# Pressure_Rig_2020-12-04_14-32-13.net
KiCad netlist of a schematic drawn in EasyEDA
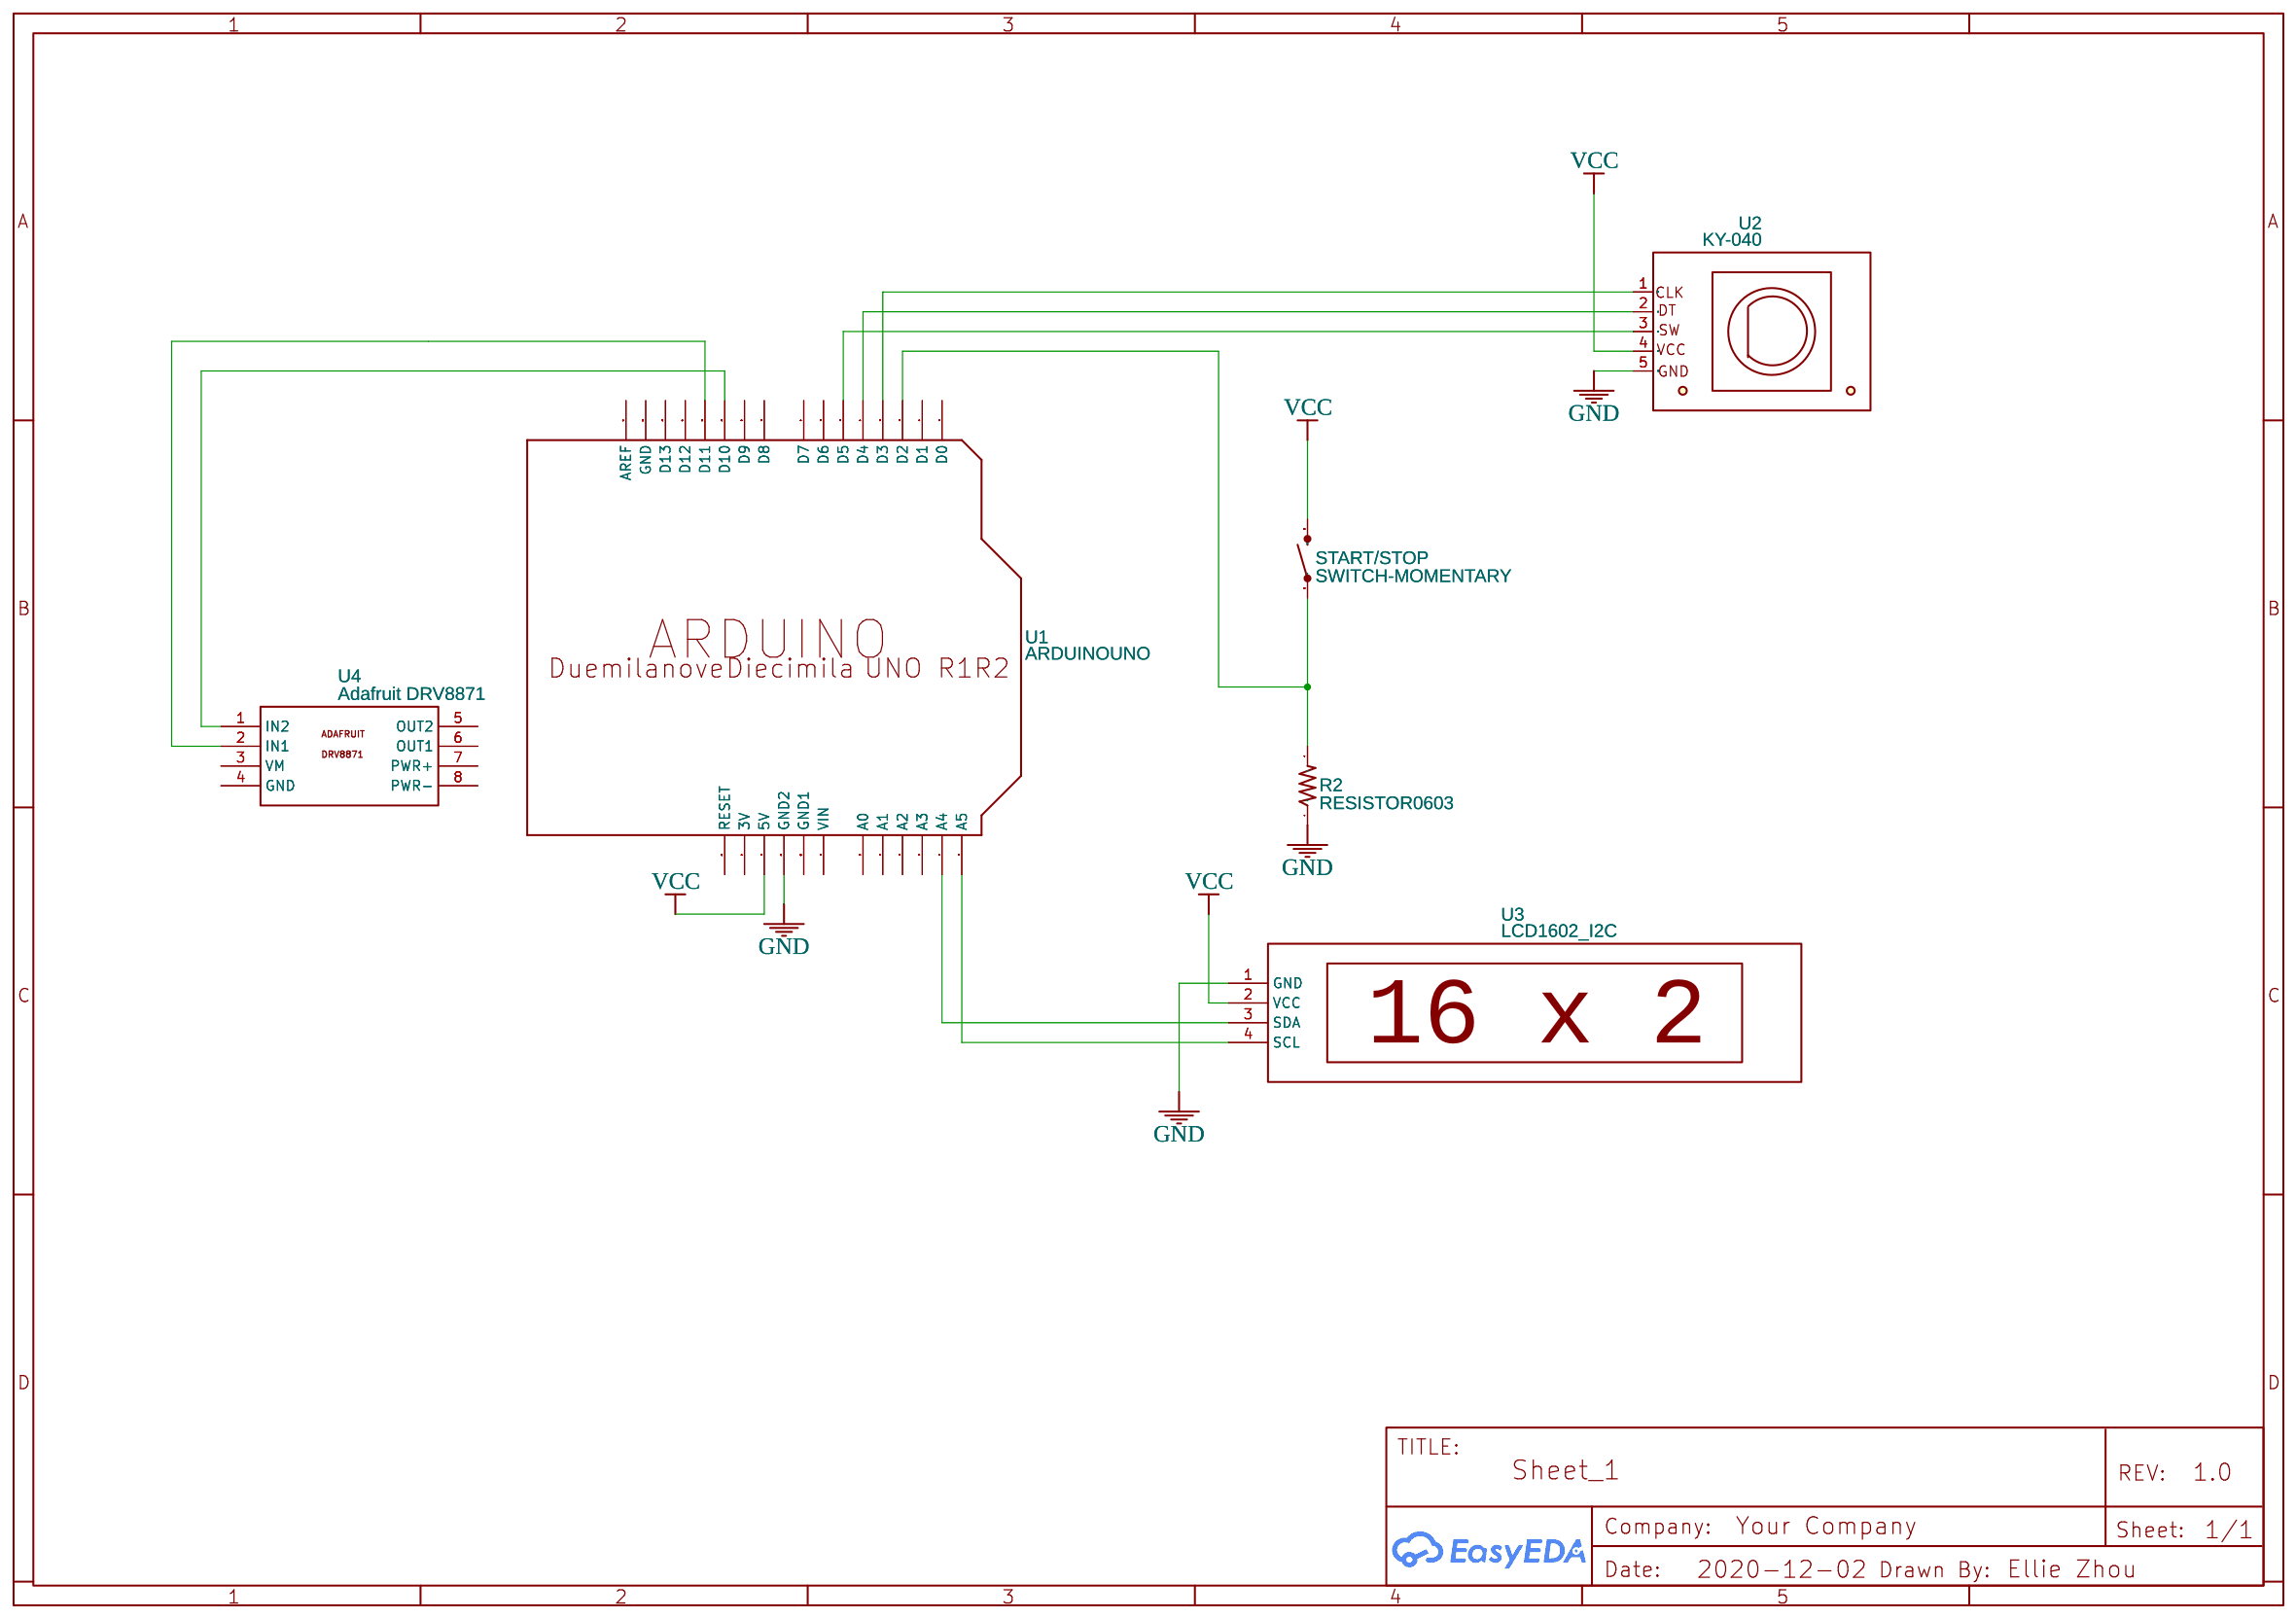
[diagram p0: schematic sheet]

(export (version "E")
  (design (tool "Eeschema 10.0.6"))
  (components
    (comp (ref "R2") (value "RESISTOR0603") (libsource (lib "") (part "RESISTOR0603")))
    (comp (ref "START/STOP") (value "SWITCH-MOMENTARY") (libsource (lib "") (part "SWITCH-MOMENTARY")))
    (comp (ref "U1") (value "ARDUINOUNO") (libsource (lib "") (part "ARDUINOUNO")))
    (comp (ref "U2") (value "KY-040") (libsource (lib "") (part "KY-040")))
    (comp (ref "U3")
      (value "LCD1602_I2C")
      (fields (field (name "BOM_Manufacturer Part") "LCD1602 I2C"))
      (libsource (lib "") (part "LCD1602_I2C"))
    )
    (comp (ref "U4")
      (value "Adafruit DRV8871")
      (fields (field (name "BOM_Manufacturer Part") "3190") (field (name "BOM_Supplier Part") "1528-1719-ND"))
      (libsource (lib "") (part "Adafruit DRV8871"))
    )
  )
  (nets
    (net (code "1") (name "GND") (class "Default")
      (node (ref "R2") (pin "1") (pinfunction "1_1") (pintype "unspecified"))
      (node (ref "U1") (pin "GND2") (pinfunction "GND2_GND2") (pintype "passive"))
      (node (ref "U2") (pin "5") (pinfunction "GND_5") (pintype "unspecified"))
      (node (ref "U3") (pin "1") (pinfunction "GND_1") (pintype "unspecified"))
    )
    (net (code "2") (name "Net-(START/STOP-1)") (class "Default")
      (node (ref "R2") (pin "2") (pinfunction "2_2") (pintype "unspecified"))
      (node (ref "START/STOP") (pin "P$1") (pinfunction "1_P$1") (pintype "unspecified"))
      (node (ref "U1") (pin "D2") (pinfunction "D2_D2") (pintype "unspecified"))
    )
    (net (code "3") (name "Net-(U2-CLK)") (class "Default")
      (node (ref "U1") (pin "D3") (pinfunction "D3_D3") (pintype "unspecified"))
      (node (ref "U2") (pin "1") (pinfunction "CLK_1") (pintype "unspecified"))
    )
    (net (code "4") (name "Net-(U2-DT)") (class "Default")
      (node (ref "U1") (pin "D4") (pinfunction "D4_D4") (pintype "unspecified"))
      (node (ref "U2") (pin "2") (pinfunction "DT_2") (pintype "unspecified"))
    )
    (net (code "5") (name "Net-(U2-SW)") (class "Default")
      (node (ref "U1") (pin "D5") (pinfunction "D5_D5") (pintype "unspecified"))
      (node (ref "U2") (pin "3") (pinfunction "SW_3") (pintype "unspecified"))
    )
    (net (code "6") (name "Net-(U3-SCL)") (class "Default")
      (node (ref "U1") (pin "A5") (pinfunction "A5_A5") (pintype "unspecified"))
      (node (ref "U3") (pin "4") (pinfunction "SCL_4") (pintype "unspecified"))
    )
    (net (code "7") (name "Net-(U3-SDA)") (class "Default")
      (node (ref "U1") (pin "A4") (pinfunction "A4_A4") (pintype "unspecified"))
      (node (ref "U3") (pin "3") (pinfunction "SDA_3") (pintype "unspecified"))
    )
    (net (code "8") (name "Net-(U4-IN1)") (class "Default")
      (node (ref "U1") (pin "D11") (pinfunction "D11_D11") (pintype "unspecified"))
      (node (ref "U4") (pin "2") (pinfunction "IN1_2") (pintype "unspecified"))
    )
    (net (code "9") (name "Net-(U4-IN2)") (class "Default")
      (node (ref "U1") (pin "D10") (pinfunction "D10_D10") (pintype "unspecified"))
      (node (ref "U4") (pin "1") (pinfunction "IN2_1") (pintype "unspecified"))
    )
    (net (code "10") (name "VCC") (class "Default")
      (node (ref "START/STOP") (pin "P$2") (pinfunction "2_P$2") (pintype "unspecified"))
      (node (ref "U1") (pin "5V") (pinfunction "5V_5V") (pintype "passive"))
      (node (ref "U2") (pin "4") (pinfunction "VCC_4") (pintype "unspecified"))
      (node (ref "U3") (pin "2") (pinfunction "VCC_2") (pintype "unspecified"))
    )
    (net (code "11") (name "unconnected-(U1-Pad3V)") (class "Default")
      (node (ref "U1") (pin "3V") (pinfunction "3V_3V") (pintype "passive"))
    )
    (net (code "12") (name "unconnected-(U1-PadA0)") (class "Default")
      (node (ref "U1") (pin "A0") (pinfunction "A0_A0") (pintype "unspecified"))
    )
    (net (code "13") (name "unconnected-(U1-PadA1)") (class "Default")
      (node (ref "U1") (pin "A1") (pinfunction "A1_A1") (pintype "unspecified"))
    )
    (net (code "14") (name "unconnected-(U1-PadA2)") (class "Default")
      (node (ref "U1") (pin "A2") (pinfunction "A2_A2") (pintype "unspecified"))
    )
    (net (code "15") (name "unconnected-(U1-PadA3)") (class "Default")
      (node (ref "U1") (pin "A3") (pinfunction "A3_A3") (pintype "unspecified"))
    )
    (net (code "16") (name "unconnected-(U1-PadAREF)") (class "Default")
      (node (ref "U1") (pin "AREF") (pinfunction "AREF_AREF") (pintype "unspecified"))
    )
    (net (code "17") (name "unconnected-(U1-PadD0)") (class "Default")
      (node (ref "U1") (pin "D0") (pinfunction "D0_D0") (pintype "unspecified"))
    )
    (net (code "18") (name "unconnected-(U1-PadD1)") (class "Default")
      (node (ref "U1") (pin "D1") (pinfunction "D1_D1") (pintype "unspecified"))
    )
    (net (code "19") (name "unconnected-(U1-PadD6)") (class "Default")
      (node (ref "U1") (pin "D6") (pinfunction "D6_D6") (pintype "unspecified"))
    )
    (net (code "20") (name "unconnected-(U1-PadD7)") (class "Default")
      (node (ref "U1") (pin "D7") (pinfunction "D7_D7") (pintype "unspecified"))
    )
    (net (code "21") (name "unconnected-(U1-PadD8)") (class "Default")
      (node (ref "U1") (pin "D8") (pinfunction "D8_D8") (pintype "unspecified"))
    )
    (net (code "22") (name "unconnected-(U1-PadD9)") (class "Default")
      (node (ref "U1") (pin "D9") (pinfunction "D9_D9") (pintype "unspecified"))
    )
    (net (code "23") (name "unconnected-(U1-PadD12)") (class "Default")
      (node (ref "U1") (pin "D12") (pinfunction "D12_D12") (pintype "unspecified"))
    )
    (net (code "24") (name "unconnected-(U1-PadD13)") (class "Default")
      (node (ref "U1") (pin "D13") (pinfunction "D13_D13") (pintype "unspecified"))
    )
    (net (code "25") (name "unconnected-(U1-PadGND)") (class "Default")
      (node (ref "U1") (pin "GND") (pinfunction "GND_GND") (pintype "passive"))
    )
    (net (code "26") (name "unconnected-(U1-PadGND1)") (class "Default")
      (node (ref "U1") (pin "GND1") (pinfunction "GND1_GND1") (pintype "passive"))
    )
    (net (code "27") (name "unconnected-(U1-PadRESET)") (class "Default")
      (node (ref "U1") (pin "RESET") (pinfunction "RESET_RESET") (pintype "unspecified"))
    )
    (net (code "28") (name "unconnected-(U1-PadVIN)") (class "Default")
      (node (ref "U1") (pin "VIN") (pinfunction "VIN_VIN") (pintype "passive"))
    )
    (net (code "29") (name "unconnected-(U4-GND-Pad4)") (class "Default")
      (node (ref "U4") (pin "4") (pinfunction "GND_4") (pintype "unspecified"))
    )
    (net (code "30") (name "unconnected-(U4-OUT1-Pad6)") (class "Default")
      (node (ref "U4") (pin "6") (pinfunction "OUT1_6") (pintype "unspecified"))
    )
    (net (code "31") (name "unconnected-(U4-OUT2-Pad5)") (class "Default")
      (node (ref "U4") (pin "5") (pinfunction "OUT2_5") (pintype "unspecified"))
    )
    (net (code "32") (name "unconnected-(U4-PWR+-Pad7)") (class "Default")
      (node (ref "U4") (pin "7") (pinfunction "PWR+_7") (pintype "unspecified"))
    )
    (net (code "33") (name "unconnected-(U4-PWR--Pad8)") (class "Default")
      (node (ref "U4") (pin "8") (pinfunction "PWR-_8") (pintype "unspecified"))
    )
    (net (code "34") (name "unconnected-(U4-VM-Pad3)") (class "Default")
      (node (ref "U4") (pin "3") (pinfunction "VM_3") (pintype "unspecified"))
    )
  )
)
